# current_sensor.net
KiCad netlist of a schematic drawn in Altium Designer
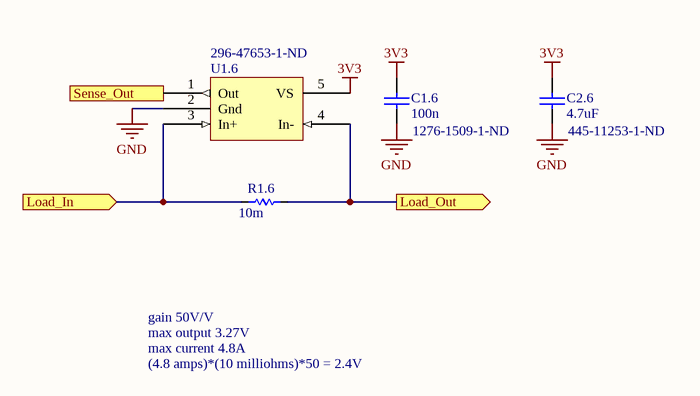
[diagram p0: current_sensor.SchDoc]

(export (version "E")
  (design (tool "Eeschema 10.0.6"))
  (components
    (comp (ref "C1.6")
      (value "100n")
      (footprint "0402")
      (fields (field (name "SUPPLIER PART NUMBER 1") "1276-1509-1-ND"))
      (libsource (lib "Luminaire") (part "CAPACITOR NON_POL"))
    )
    (comp (ref "C2.6")
      (value "4.7uF")
      (footprint "1608[0603]")
      (description "derates to 2.2")
      (fields (field (name "SUPPLIER PART NUMBER 1") "445-11253-1-ND"))
      (libsource (lib "KEMET Chip Capacitor") (part "C0402"))
    )
    (comp (ref "R1.6") (value "10m") (footprint "0805") (libsource (lib "Luminaire") (part "RESISTOR")))
    (comp (ref "U1.6")
      (value "~")
      (footprint "SOT23-5")
      (description "Current Sense Amp")
      (fields (field (name "SUPPLIER PART NUMBER 1") "296-47653-1-ND"))
      (libsource (lib "Luminaire") (part "INA180"))
    )
  )
  (nets
    (net (code "1") (name "/Load_In") (class "Default")
      (node (ref "R1.6") (pin "2") (pinfunction "2_2") (pintype "passive"))
      (node (ref "U1.6") (pin "3") (pinfunction "In+_3") (pintype "input"))
    )
    (net (code "2") (name "/Load_Out") (class "Default")
      (node (ref "R1.6") (pin "1") (pinfunction "1_1") (pintype "passive"))
      (node (ref "U1.6") (pin "4") (pinfunction "In-_4") (pintype "input"))
    )
    (net (code "3") (name "/Sense_Out") (class "Default")
      (node (ref "U1.6") (pin "1") (pinfunction "Out_1") (pintype "output"))
    )
    (net (code "4") (name "3V3") (class "Default")
      (node (ref "C1.6") (pin "1") (pinfunction "1_1") (pintype "passive"))
      (node (ref "C2.6") (pin "2") (pinfunction "2_2") (pintype "passive"))
      (node (ref "U1.6") (pin "5") (pinfunction "VS_5") (pintype "power_in"))
    )
    (net (code "5") (name "GND") (class "Default")
      (node (ref "C1.6") (pin "2") (pinfunction "2_2") (pintype "passive"))
      (node (ref "C2.6") (pin "1") (pinfunction "1_1") (pintype "passive"))
      (node (ref "U1.6") (pin "2") (pinfunction "Gnd_2") (pintype "power_in"))
    )
  )
)
